# bno_aux.net
KiCad netlist of a schematic drawn in Altium Designer
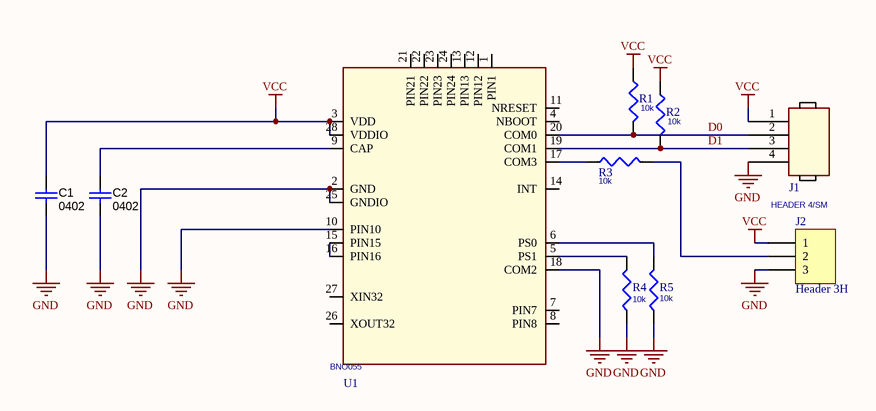
[diagram p0: bno_aux.SchDoc]

(export (version "E")
  (design (tool "Eeschema 10.0.6"))
  (components
    (comp (ref "C1")
      (value "885012205037")
      (footprint "CAPC0402N")
      (description "CAP, CERM, 0.1 µF, 16 V, +/- 10%, X7R, 0402")
      (fields
        (field (name "MANUFACTURER") "Wurth Elektronik")
        (field (name "CAP_CASE") "0402")
        (field (name "PUBLISHER") "Texas Instruments")
      )
      (libsource (lib "SLEEPTRACK2_PHASE3_Library") (part "885012205037"))
    )
    (comp (ref "C2")
      (value "885012205037")
      (footprint "CAPC0402N")
      (description "CAP, CERM, 0.1 µF, 16 V, +/- 10%, X7R, 0402")
      (fields
        (field (name "MANUFACTURER") "Wurth Elektronik")
        (field (name "CAP_CASE") "0402")
        (field (name "PUBLISHER") "Texas Instruments")
      )
      (libsource (lib "SLEEPTRACK2_PHASE3_Library") (part "885012205037"))
    )
    (comp (ref "J1")
      (value "HEADER 4/SM")
      (footprint "61900411021")
      (libsource (lib "SLEEPTRACK2_PHASE3_Library") (part "HEADER 4/SM"))
    )
    (comp (ref "J2")
      (value "Header 3H")
      (footprint "Phase4:SolderJumper")
      (description "Header, 3-Pin, Right Angle")
      (fields (field (name "PUBLISHER") "Altium Limited"))
      (libsource (lib "Miscellaneous Connectors") (part "Header 3H"))
    )
    (comp (ref "R1")
      (value "10k")
      (footprint "RESC402N")
      (description "RES SMD 10K OHM 1% 1/16W 0402")
      (libsource (lib "SLEEPTRACK2_PHASE3_Library") (part "RC0402FR-0710KL"))
    )
    (comp (ref "R2")
      (value "10k")
      (footprint "RESC402N")
      (description "RES SMD 10K OHM 1% 1/16W 0402")
      (libsource (lib "SLEEPTRACK2_PHASE3_Library") (part "RC0402FR-0710KL"))
    )
    (comp (ref "R3")
      (value "10k")
      (footprint "RESC402N")
      (description "RES SMD 10K OHM 1% 1/16W 0402")
      (libsource (lib "SLEEPTRACK2_PHASE3_Library") (part "RC0402FR-0710KL"))
    )
    (comp (ref "R4")
      (value "10k")
      (footprint "RESC402N")
      (description "RES SMD 10K OHM 1% 1/16W 0402")
      (libsource (lib "SLEEPTRACK2_PHASE3_Library") (part "RC0402FR-0710KL"))
    )
    (comp (ref "R5")
      (value "10k")
      (footprint "RESC402N")
      (description "RES SMD 10K OHM 1% 1/16W 0402")
      (libsource (lib "SLEEPTRACK2_PHASE3_Library") (part "RC0402FR-0710KL"))
    )
    (comp (ref "U1")
      (value "BNO055")
      (footprint "LCCS50P520X380X118-28N")
      (libsource (lib "SLEEPTRACK2_PHASE3_Library") (part "BNO055"))
    )
  )
  (nets
    (net (code "1") (name "/D0") (class "Default")
      (node (ref "J1") (pin "2") (pinfunction "2_2") (pintype "passive"))
      (node (ref "R1") (pin "2") (pinfunction "2_2") (pintype "passive"))
      (node (ref "U1") (pin "20") (pinfunction "COM0_20") (pintype "passive"))
    )
    (net (code "2") (name "/D1") (class "Default")
      (node (ref "J1") (pin "3") (pinfunction "3_3") (pintype "passive"))
      (node (ref "R2") (pin "2") (pinfunction "2_2") (pintype "passive"))
      (node (ref "U1") (pin "19") (pinfunction "COM1_19") (pintype "passive"))
    )
    (net (code "3") (name "GND") (class "Default")
      (node (ref "C1") (pin "2") (pinfunction "2_2") (pintype "passive"))
      (node (ref "C2") (pin "2") (pinfunction "2_2") (pintype "passive"))
      (node (ref "J1") (pin "4") (pinfunction "4_4") (pintype "passive"))
      (node (ref "J2") (pin "3") (pinfunction "3_3") (pintype "passive"))
      (node (ref "R4") (pin "1") (pinfunction "1_1") (pintype "passive"))
      (node (ref "R5") (pin "1") (pinfunction "1_1") (pintype "passive"))
      (node (ref "U1") (pin "10") (pinfunction "PIN10_10") (pintype "passive"))
      (node (ref "U1") (pin "18") (pinfunction "COM2_18") (pintype "passive"))
      (node (ref "U1") (pin "2") (pinfunction "GND_2") (pintype "passive"))
      (node (ref "U1") (pin "25") (pinfunction "GNDIO_25") (pintype "passive"))
    )
    (net (code "4") (name "Net-(J2-Pad2)") (class "Default")
      (node (ref "J2") (pin "2") (pinfunction "2_2") (pintype "passive"))
      (node (ref "R3") (pin "2") (pinfunction "2_2") (pintype "passive"))
    )
    (net (code "5") (name "Net-(U1-CAP)") (class "Default")
      (node (ref "C2") (pin "1") (pinfunction "1_1") (pintype "passive"))
      (node (ref "U1") (pin "9") (pinfunction "CAP_9") (pintype "passive"))
    )
    (net (code "6") (name "Net-(U1-COM3)") (class "Default")
      (node (ref "R3") (pin "1") (pinfunction "1_1") (pintype "passive"))
      (node (ref "U1") (pin "17") (pinfunction "COM3_17") (pintype "passive"))
    )
    (net (code "7") (name "Net-(U1-PIN15)") (class "Default")
      (node (ref "U1") (pin "15") (pinfunction "PIN15_15") (pintype "passive"))
      (node (ref "U1") (pin "16") (pinfunction "PIN16_16") (pintype "passive"))
    )
    (net (code "8") (name "Net-(U1-PS0)") (class "Default")
      (node (ref "R5") (pin "2") (pinfunction "2_2") (pintype "passive"))
      (node (ref "U1") (pin "6") (pinfunction "PS0_6") (pintype "passive"))
    )
    (net (code "9") (name "Net-(U1-PS1)") (class "Default")
      (node (ref "R4") (pin "2") (pinfunction "2_2") (pintype "passive"))
      (node (ref "U1") (pin "5") (pinfunction "PS1_5") (pintype "passive"))
    )
    (net (code "10") (name "VCC") (class "Default")
      (node (ref "C1") (pin "1") (pinfunction "1_1") (pintype "passive"))
      (node (ref "J1") (pin "1") (pinfunction "1_1") (pintype "passive"))
      (node (ref "J2") (pin "1") (pinfunction "1_1") (pintype "passive"))
      (node (ref "R1") (pin "1") (pinfunction "1_1") (pintype "passive"))
      (node (ref "R2") (pin "1") (pinfunction "1_1") (pintype "passive"))
      (node (ref "U1") (pin "28") (pinfunction "VDDIO_28") (pintype "passive"))
      (node (ref "U1") (pin "3") (pinfunction "VDD_3") (pintype "passive"))
    )
    (net (code "11") (name "unconnected-(U1-INT-Pad14)") (class "Default")
      (node (ref "U1") (pin "14") (pinfunction "INT_14") (pintype "passive"))
    )
    (net (code "12") (name "unconnected-(U1-NBOOT-Pad4)") (class "Default")
      (node (ref "U1") (pin "4") (pinfunction "NBOOT_4") (pintype "passive"))
    )
    (net (code "13") (name "unconnected-(U1-NRESET-Pad11)") (class "Default")
      (node (ref "U1") (pin "11") (pinfunction "NRESET_11") (pintype "passive"))
    )
    (net (code "14") (name "unconnected-(U1-PIN1-Pad1)") (class "Default")
      (node (ref "U1") (pin "1") (pinfunction "PIN1_1") (pintype "passive"))
    )
    (net (code "15") (name "unconnected-(U1-PIN7-Pad7)") (class "Default")
      (node (ref "U1") (pin "7") (pinfunction "PIN7_7") (pintype "passive"))
    )
    (net (code "16") (name "unconnected-(U1-PIN8-Pad8)") (class "Default")
      (node (ref "U1") (pin "8") (pinfunction "PIN8_8") (pintype "passive"))
    )
    (net (code "17") (name "unconnected-(U1-PIN12-Pad12)") (class "Default")
      (node (ref "U1") (pin "12") (pinfunction "PIN12_12") (pintype "passive"))
    )
    (net (code "18") (name "unconnected-(U1-PIN13-Pad13)") (class "Default")
      (node (ref "U1") (pin "13") (pinfunction "PIN13_13") (pintype "passive"))
    )
    (net (code "19") (name "unconnected-(U1-PIN21-Pad21)") (class "Default")
      (node (ref "U1") (pin "21") (pinfunction "PIN21_21") (pintype "passive"))
    )
    (net (code "20") (name "unconnected-(U1-PIN22-Pad22)") (class "Default")
      (node (ref "U1") (pin "22") (pinfunction "PIN22_22") (pintype "passive"))
    )
    (net (code "21") (name "unconnected-(U1-PIN23-Pad23)") (class "Default")
      (node (ref "U1") (pin "23") (pinfunction "PIN23_23") (pintype "passive"))
    )
    (net (code "22") (name "unconnected-(U1-PIN24-Pad24)") (class "Default")
      (node (ref "U1") (pin "24") (pinfunction "PIN24_24") (pintype "passive"))
    )
    (net (code "23") (name "unconnected-(U1-XIN32-Pad27)") (class "Default")
      (node (ref "U1") (pin "27") (pinfunction "XIN32_27") (pintype "passive"))
    )
    (net (code "24") (name "unconnected-(U1-XOUT32-Pad26)") (class "Default")
      (node (ref "U1") (pin "26") (pinfunction "XOUT32_26") (pintype "passive"))
    )
  )
)
